# SFP.net
KiCad netlist of a schematic drawn in Altium Designer
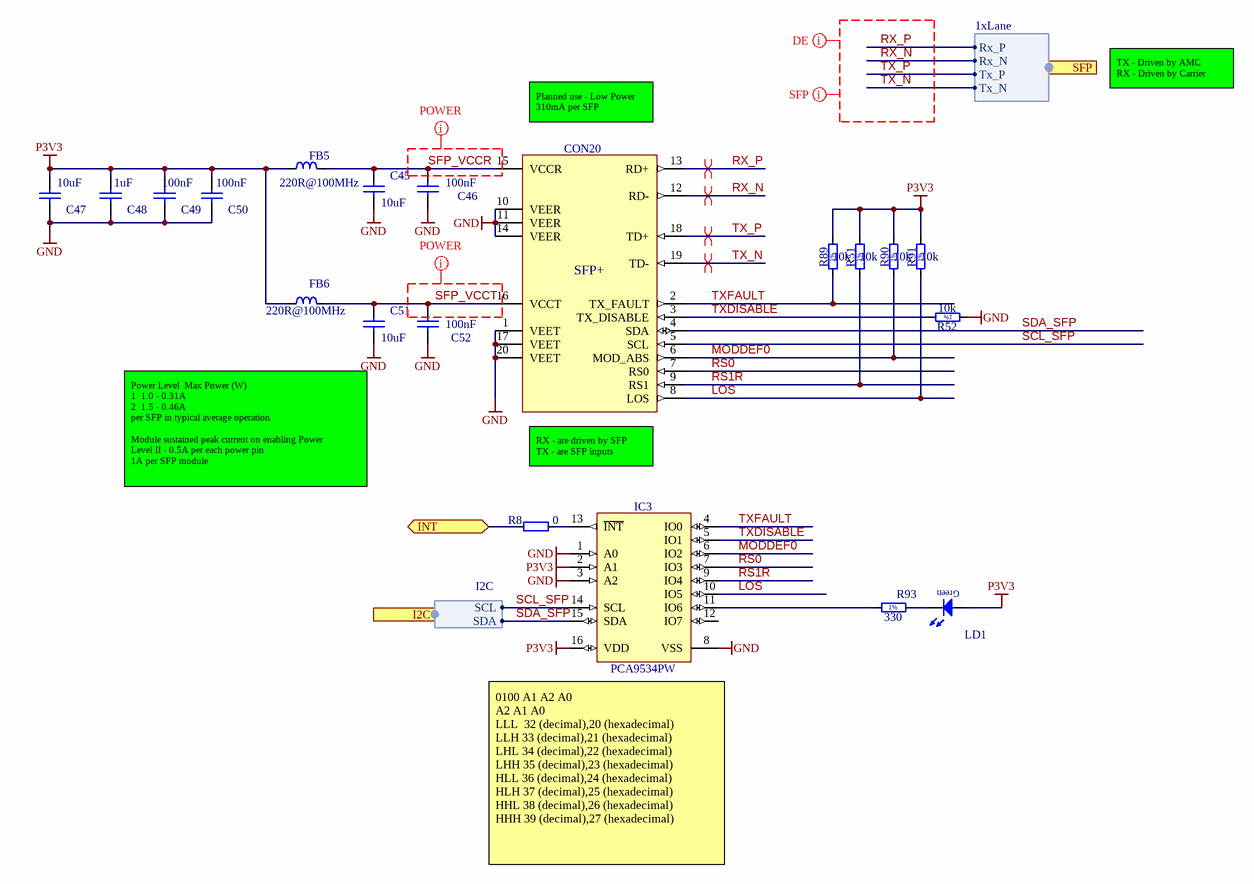
[diagram p0: SFP.SchDoc]

(export (version "E")
  (design (tool "Eeschema 10.0.6"))
  (components
    (comp (ref "C45")
      (value "10uF")
      (footprint "CAPC2012X135N")
      (description "Non-polarised capacitor")
      (fields
        (field (name "PART NUMBER") "CC0805_10UF_10V_10%_X7R")
        (field (name "VOLTAGE") "10V")
        (field (name "AUTHOR") "CERN DEM JLC")
      )
      (libsource (lib "Capacitors") (part "Capacitor - non polarized"))
    )
    (comp (ref "C46")
      (value "100nF")
      (footprint "CAPC1005X55N")
      (description "Non-polarised capacitor")
      (fields
        (field (name "PART NUMBER") "CC0402_100NF_16V_10%_X5R")
        (field (name "VOLTAGE") "16V")
        (field (name "AUTHOR") "CERN DEM JLC")
      )
      (libsource (lib "Capacitors") (part "Capacitor - non polarized"))
    )
    (comp (ref "C47")
      (value "10uF")
      (footprint "CAPC2012X135N")
      (description "Non-polarised capacitor")
      (fields
        (field (name "PART NUMBER") "CC0805_10UF_10V_10%_X7R")
        (field (name "VOLTAGE") "10V")
        (field (name "AUTHOR") "CERN DEM JLC")
      )
      (libsource (lib "Capacitors") (part "Capacitor - non polarized"))
    )
    (comp (ref "C48")
      (value "1uF")
      (footprint "CAPC1608X87N")
      (description "Non-polarised capacitor")
      (fields
        (field (name "PART NUMBER") "CC0603_1UF_25V_10%_X7R")
        (field (name "VOLTAGE") "25V")
        (field (name "AUTHOR") "CERN DEM JLC")
      )
      (libsource (lib "Capacitors") (part "Capacitor - non polarized"))
    )
    (comp (ref "C49")
      (value "100nF")
      (footprint "CAPC1005X55N")
      (description "Non-polarised capacitor")
      (fields
        (field (name "PART NUMBER") "CC0402_100NF_16V_10%_X5R")
        (field (name "VOLTAGE") "16V")
        (field (name "AUTHOR") "CERN DEM JLC")
      )
      (libsource (lib "Capacitors") (part "Capacitor - non polarized"))
    )
    (comp (ref "C50")
      (value "100nF")
      (footprint "CAPC1005X55N")
      (description "Non-polarised capacitor")
      (fields
        (field (name "PART NUMBER") "CC0402_100NF_16V_10%_X5R")
        (field (name "VOLTAGE") "16V")
        (field (name "AUTHOR") "CERN DEM JLC")
      )
      (libsource (lib "Capacitors") (part "Capacitor - non polarized"))
    )
    (comp (ref "C51")
      (value "10uF")
      (footprint "CAPC2012X135N")
      (description "Non-polarised capacitor")
      (fields
        (field (name "PART NUMBER") "CC0805_10UF_10V_10%_X7R")
        (field (name "VOLTAGE") "10V")
        (field (name "AUTHOR") "CERN DEM JLC")
      )
      (libsource (lib "Capacitors") (part "Capacitor - non polarized"))
    )
    (comp (ref "C52")
      (value "100nF")
      (footprint "CAPC1005X55N")
      (description "Non-polarised capacitor")
      (fields
        (field (name "PART NUMBER") "CC0402_100NF_16V_10%_X5R")
        (field (name "VOLTAGE") "16V")
        (field (name "AUTHOR") "CERN DEM JLC")
      )
      (libsource (lib "Capacitors") (part "Capacitor - non polarized"))
    )
    (comp (ref "CON20")
      (value "1888247-1")
      (footprint "TYCO_1888247-1")
      (description "20 Position SFP+ Connector (Small Form-factor Pluggable)")
      (fields
        (field (name "PART NUMBER") "TYCO_1888247-1")
        (field (name "MANUFACTURER") "TYCO ELECTRONICS")
        (field (name "AUTHOR") "CERN DEM JLC")
      )
      (libsource (lib "Connectors") (part "SFP+x1"))
    )
    (comp (ref "FB5")
      (value "220R@100MHz")
      (footprint "INDC2012X105N")
      (description "Inductor")
      (fields
        (field (name "PART NUMBER") "IND0805_MURATA_BLM21PG221SN1D")
        (field (name "POWER") "2A")
        (field (name "AUTHOR") "CERN DEM JLC")
      )
      (libsource (lib "Inductors & Transformers") (part "Inductor"))
    )
    (comp (ref "FB6")
      (value "220R@100MHz")
      (footprint "INDC2012X105N")
      (description "Inductor")
      (fields
        (field (name "PART NUMBER") "IND0805_MURATA_BLM21PG221SN1D")
        (field (name "POWER") "2A")
        (field (name "AUTHOR") "CERN DEM JLC")
      )
      (libsource (lib "Inductors & Transformers") (part "Inductor"))
    )
    (comp (ref "IC3")
      (value "PCA9534PW")
      (footprint "SOP65P640X110-16N")
      (description "8-Bit I2C-Bus and SMBus Low Power I/O Port with Interrupt")
      (fields (field (name "MANUFACTURER") "ANALOG DEVICES") (field (name "AUTHOR") "CERN DEM JLC"))
      (libsource (lib "ICs And Semiconductors") (part "PCA9534PW"))
    )
    (comp (ref "LD1")
      (value "LED_AVAGO_HSME-C120")
      (footprint "LED_AVAGO_HSME-C120")
      (description "LED Green 1C 2A")
      (fields
        (field (name "MANUFACTURER") "AVAGO TECHNOLOGIES")
        (field (name "MANUFACTURER PART NUMBER") "HSME-C120")
        (field (name "AUTHOR") "CERN DEM JMW")
      )
      (libsource (lib "ICs And Semiconductors") (part "LED Green 1C 2A"))
    )
    (comp (ref "R8")
      (value "0")
      (footprint "RESC1005X40N")
      (description "Resistor")
      (fields
        (field (name "PART NUMBER") "R0402_0R_JUMPER")
        (field (name "MANUFACTURER") "GENERIC")
        (field (name "AUTHOR") "CERN DEM JLC")
      )
      (libsource (lib "Resistors") (part "Resistor"))
    )
    (comp (ref "R51")
      (value "10k")
      (footprint "RESC1005X40N")
      (description "Resistor - 1%")
      (fields
        (field (name "PART NUMBER") "R0402_10K_1%_0.0625W_100PPM")
        (field (name "POWER") "0.0625W")
        (field (name "AUTHOR") "CERN DEM JLC")
      )
      (libsource (lib "Resistors") (part "Resistor - 1%"))
    )
    (comp (ref "R52")
      (value "10k")
      (footprint "RESC1005X40N")
      (description "Resistor - 1%")
      (fields
        (field (name "PART NUMBER") "R0402_10K_1%_0.0625W_100PPM")
        (field (name "POWER") "0.0625W")
        (field (name "AUTHOR") "CERN DEM JLC")
      )
      (libsource (lib "Resistors") (part "Resistor - 1%"))
    )
    (comp (ref "R89")
      (value "10k")
      (footprint "RESC1005X40N")
      (description "Resistor - 1%")
      (fields
        (field (name "PART NUMBER") "R0402_10K_1%_0.0625W_100PPM")
        (field (name "POWER") "0.0625W")
        (field (name "AUTHOR") "CERN DEM JLC")
      )
      (libsource (lib "Resistors") (part "Resistor - 1%"))
    )
    (comp (ref "R90")
      (value "10k")
      (footprint "RESC1005X40N")
      (description "Resistor - 1%")
      (fields
        (field (name "PART NUMBER") "R0402_10K_1%_0.0625W_100PPM")
        (field (name "POWER") "0.0625W")
        (field (name "AUTHOR") "CERN DEM JLC")
      )
      (libsource (lib "Resistors") (part "Resistor - 1%"))
    )
    (comp (ref "R91")
      (value "10k")
      (footprint "RESC1005X40N")
      (description "Resistor - 1%")
      (fields
        (field (name "PART NUMBER") "R0402_10K_1%_0.0625W_100PPM")
        (field (name "POWER") "0.0625W")
        (field (name "AUTHOR") "CERN DEM JLC")
      )
      (libsource (lib "Resistors") (part "Resistor - 1%"))
    )
    (comp (ref "R93")
      (value "330")
      (footprint "RESC1608X55N")
      (description "Resistor - 1%")
      (fields
        (field (name "PART NUMBER") "R0603_330R_1%_0.1W_100PPM")
        (field (name "POWER") "0.1W")
        (field (name "AUTHOR") "CERN DEM JLC")
      )
      (libsource (lib "Resistors") (part "Resistor - 1%"))
    )
  )
  (nets
    (net (code "3") (name "/INT") (class "Default")
      (node (ref "R8") (pin "1") (pinfunction "1_1") (pintype "passive"))
    )
    (net (code "4") (name "/LOS") (class "Default")
      (node (ref "CON20") (pin "8") (pinfunction "LOS_8") (pintype "output"))
      (node (ref "IC3") (pin "10") (pinfunction "IO5_10") (pintype "bidirectional"))
      (node (ref "R91") (pin "1") (pinfunction "1_1") (pintype "passive"))
    )
    (net (code "5") (name "/MODDEF0") (class "Default")
      (node (ref "CON20") (pin "6") (pinfunction "MOD_ABS_6") (pintype "output"))
      (node (ref "IC3") (pin "6") (pinfunction "IO2_6") (pintype "bidirectional"))
      (node (ref "R90") (pin "1") (pinfunction "1_1") (pintype "passive"))
    )
    (net (code "6") (name "/RS0") (class "Default")
      (node (ref "CON20") (pin "7") (pinfunction "RS0_7") (pintype "input"))
      (node (ref "IC3") (pin "7") (pinfunction "IO3_7") (pintype "bidirectional"))
    )
    (net (code "7") (name "/RS1R") (class "Default")
      (node (ref "CON20") (pin "9") (pinfunction "RS1_9") (pintype "input"))
      (node (ref "IC3") (pin "9") (pinfunction "IO4_9") (pintype "bidirectional"))
      (node (ref "R51") (pin "1") (pinfunction "1_1") (pintype "passive"))
    )
    (net (code "8") (name "/RX_N") (class "Default")
      (node (ref "CON20") (pin "12") (pinfunction "RD-_12") (pintype "output"))
    )
    (net (code "9") (name "/RX_P") (class "Default")
      (node (ref "CON20") (pin "13") (pinfunction "RD+_13") (pintype "output"))
    )
    (net (code "10") (name "/SCL_SFP") (class "Default")
      (node (ref "CON20") (pin "5") (pinfunction "SCL_5") (pintype "input"))
      (node (ref "IC3") (pin "14") (pinfunction "SCL_14") (pintype "input"))
    )
    (net (code "11") (name "/SDA_SFP") (class "Default")
      (node (ref "CON20") (pin "4") (pinfunction "SDA_4") (pintype "bidirectional"))
      (node (ref "IC3") (pin "15") (pinfunction "SDA_15") (pintype "bidirectional"))
    )
    (net (code "12") (name "/SFP_VCCR") (class "Default")
      (node (ref "C45") (pin "1") (pinfunction "1_1") (pintype "passive"))
      (node (ref "C46") (pin "1") (pinfunction "1_1") (pintype "passive"))
      (node (ref "CON20") (pin "15") (pinfunction "VCCR_15") (pintype "power_in"))
      (node (ref "FB5") (pin "2") (pinfunction "2_2") (pintype "passive"))
    )
    (net (code "13") (name "/SFP_VCCT") (class "Default")
      (node (ref "C51") (pin "1") (pinfunction "1_1") (pintype "passive"))
      (node (ref "C52") (pin "1") (pinfunction "1_1") (pintype "passive"))
      (node (ref "CON20") (pin "16") (pinfunction "VCCT_16") (pintype "power_in"))
      (node (ref "FB6") (pin "2") (pinfunction "2_2") (pintype "passive"))
    )
    (net (code "14") (name "/TXDISABLE") (class "Default")
      (node (ref "CON20") (pin "3") (pinfunction "TX_DISABLE_3") (pintype "input"))
      (node (ref "IC3") (pin "5") (pinfunction "IO1_5") (pintype "bidirectional"))
      (node (ref "R52") (pin "2") (pinfunction "2_2") (pintype "passive"))
    )
    (net (code "15") (name "/TXFAULT") (class "Default")
      (node (ref "CON20") (pin "2") (pinfunction "TX_FAULT_2") (pintype "output"))
      (node (ref "IC3") (pin "4") (pinfunction "IO0_4") (pintype "bidirectional"))
      (node (ref "R89") (pin "1") (pinfunction "1_1") (pintype "passive"))
    )
    (net (code "16") (name "/TX_N") (class "Default")
      (node (ref "CON20") (pin "19") (pinfunction "TD-_19") (pintype "input"))
    )
    (net (code "17") (name "/TX_P") (class "Default")
      (node (ref "CON20") (pin "18") (pinfunction "TD+_18") (pintype "input"))
    )
    (net (code "20") (name "GND") (class "Default")
      (node (ref "C45") (pin "2") (pinfunction "2_2") (pintype "passive"))
      (node (ref "C46") (pin "2") (pinfunction "2_2") (pintype "passive"))
      (node (ref "C47") (pin "2") (pinfunction "2_2") (pintype "passive"))
      (node (ref "C48") (pin "1") (pinfunction "1_1") (pintype "passive"))
      (node (ref "C49") (pin "2") (pinfunction "2_2") (pintype "passive"))
      (node (ref "C50") (pin "2") (pinfunction "2_2") (pintype "passive"))
      (node (ref "C51") (pin "2") (pinfunction "2_2") (pintype "passive"))
      (node (ref "C52") (pin "2") (pinfunction "2_2") (pintype "passive"))
      (node (ref "CON20") (pin "1") (pinfunction "VEET_1") (pintype "power_in"))
      (node (ref "CON20") (pin "10") (pinfunction "VEER_10") (pintype "power_in"))
      (node (ref "CON20") (pin "11") (pinfunction "VEER_11") (pintype "power_in"))
      (node (ref "CON20") (pin "14") (pinfunction "VEER_14") (pintype "power_in"))
      (node (ref "CON20") (pin "17") (pinfunction "VEET_17") (pintype "power_in"))
      (node (ref "CON20") (pin "20") (pinfunction "VEET_20") (pintype "power_in"))
      (node (ref "IC3") (pin "1") (pinfunction "A0_1") (pintype "input"))
      (node (ref "IC3") (pin "3") (pinfunction "A2_3") (pintype "input"))
      (node (ref "IC3") (pin "8") (pinfunction "VSS_8") (pintype "power_in"))
      (node (ref "R52") (pin "1") (pinfunction "1_1") (pintype "passive"))
    )
    (net (code "21") (name "Net-(IC3-IO6)") (class "Default")
      (node (ref "IC3") (pin "11") (pinfunction "IO6_11") (pintype "bidirectional"))
      (node (ref "R93") (pin "1") (pinfunction "1_1") (pintype "passive"))
    )
    (net (code "22") (name "Net-(IC3-~{INT})") (class "Default")
      (node (ref "IC3") (pin "13") (pinfunction "~{INT}_13") (pintype "output"))
      (node (ref "R8") (pin "2") (pinfunction "2_2") (pintype "passive"))
    )
    (net (code "23") (name "Net-(LD1-C)") (class "Default")
      (node (ref "LD1") (pin "1") (pinfunction "C_1") (pintype "passive"))
      (node (ref "R93") (pin "2") (pinfunction "2_2") (pintype "passive"))
    )
    (net (code "24") (name "P3V3") (class "Default")
      (node (ref "C47") (pin "1") (pinfunction "1_1") (pintype "passive"))
      (node (ref "C48") (pin "2") (pinfunction "2_2") (pintype "passive"))
      (node (ref "C49") (pin "1") (pinfunction "1_1") (pintype "passive"))
      (node (ref "C50") (pin "1") (pinfunction "1_1") (pintype "passive"))
      (node (ref "FB5") (pin "1") (pinfunction "1_1") (pintype "passive"))
      (node (ref "FB6") (pin "1") (pinfunction "1_1") (pintype "passive"))
      (node (ref "IC3") (pin "16") (pinfunction "VDD_16") (pintype "bidirectional"))
      (node (ref "IC3") (pin "2") (pinfunction "A1_2") (pintype "input"))
      (node (ref "LD1") (pin "2") (pinfunction "A_2") (pintype "passive"))
      (node (ref "R51") (pin "2") (pinfunction "2_2") (pintype "passive"))
      (node (ref "R89") (pin "2") (pinfunction "2_2") (pintype "passive"))
      (node (ref "R90") (pin "2") (pinfunction "2_2") (pintype "passive"))
      (node (ref "R91") (pin "2") (pinfunction "2_2") (pintype "passive"))
    )
    (net (code "25") (name "unconnected-(IC3-IO7-Pad12)") (class "Default")
      (node (ref "IC3") (pin "12") (pinfunction "IO7_12") (pintype "bidirectional"))
    )
  )
)
